# DDS_OUT_channel.net
KiCad netlist of a schematic drawn in Altium Designer
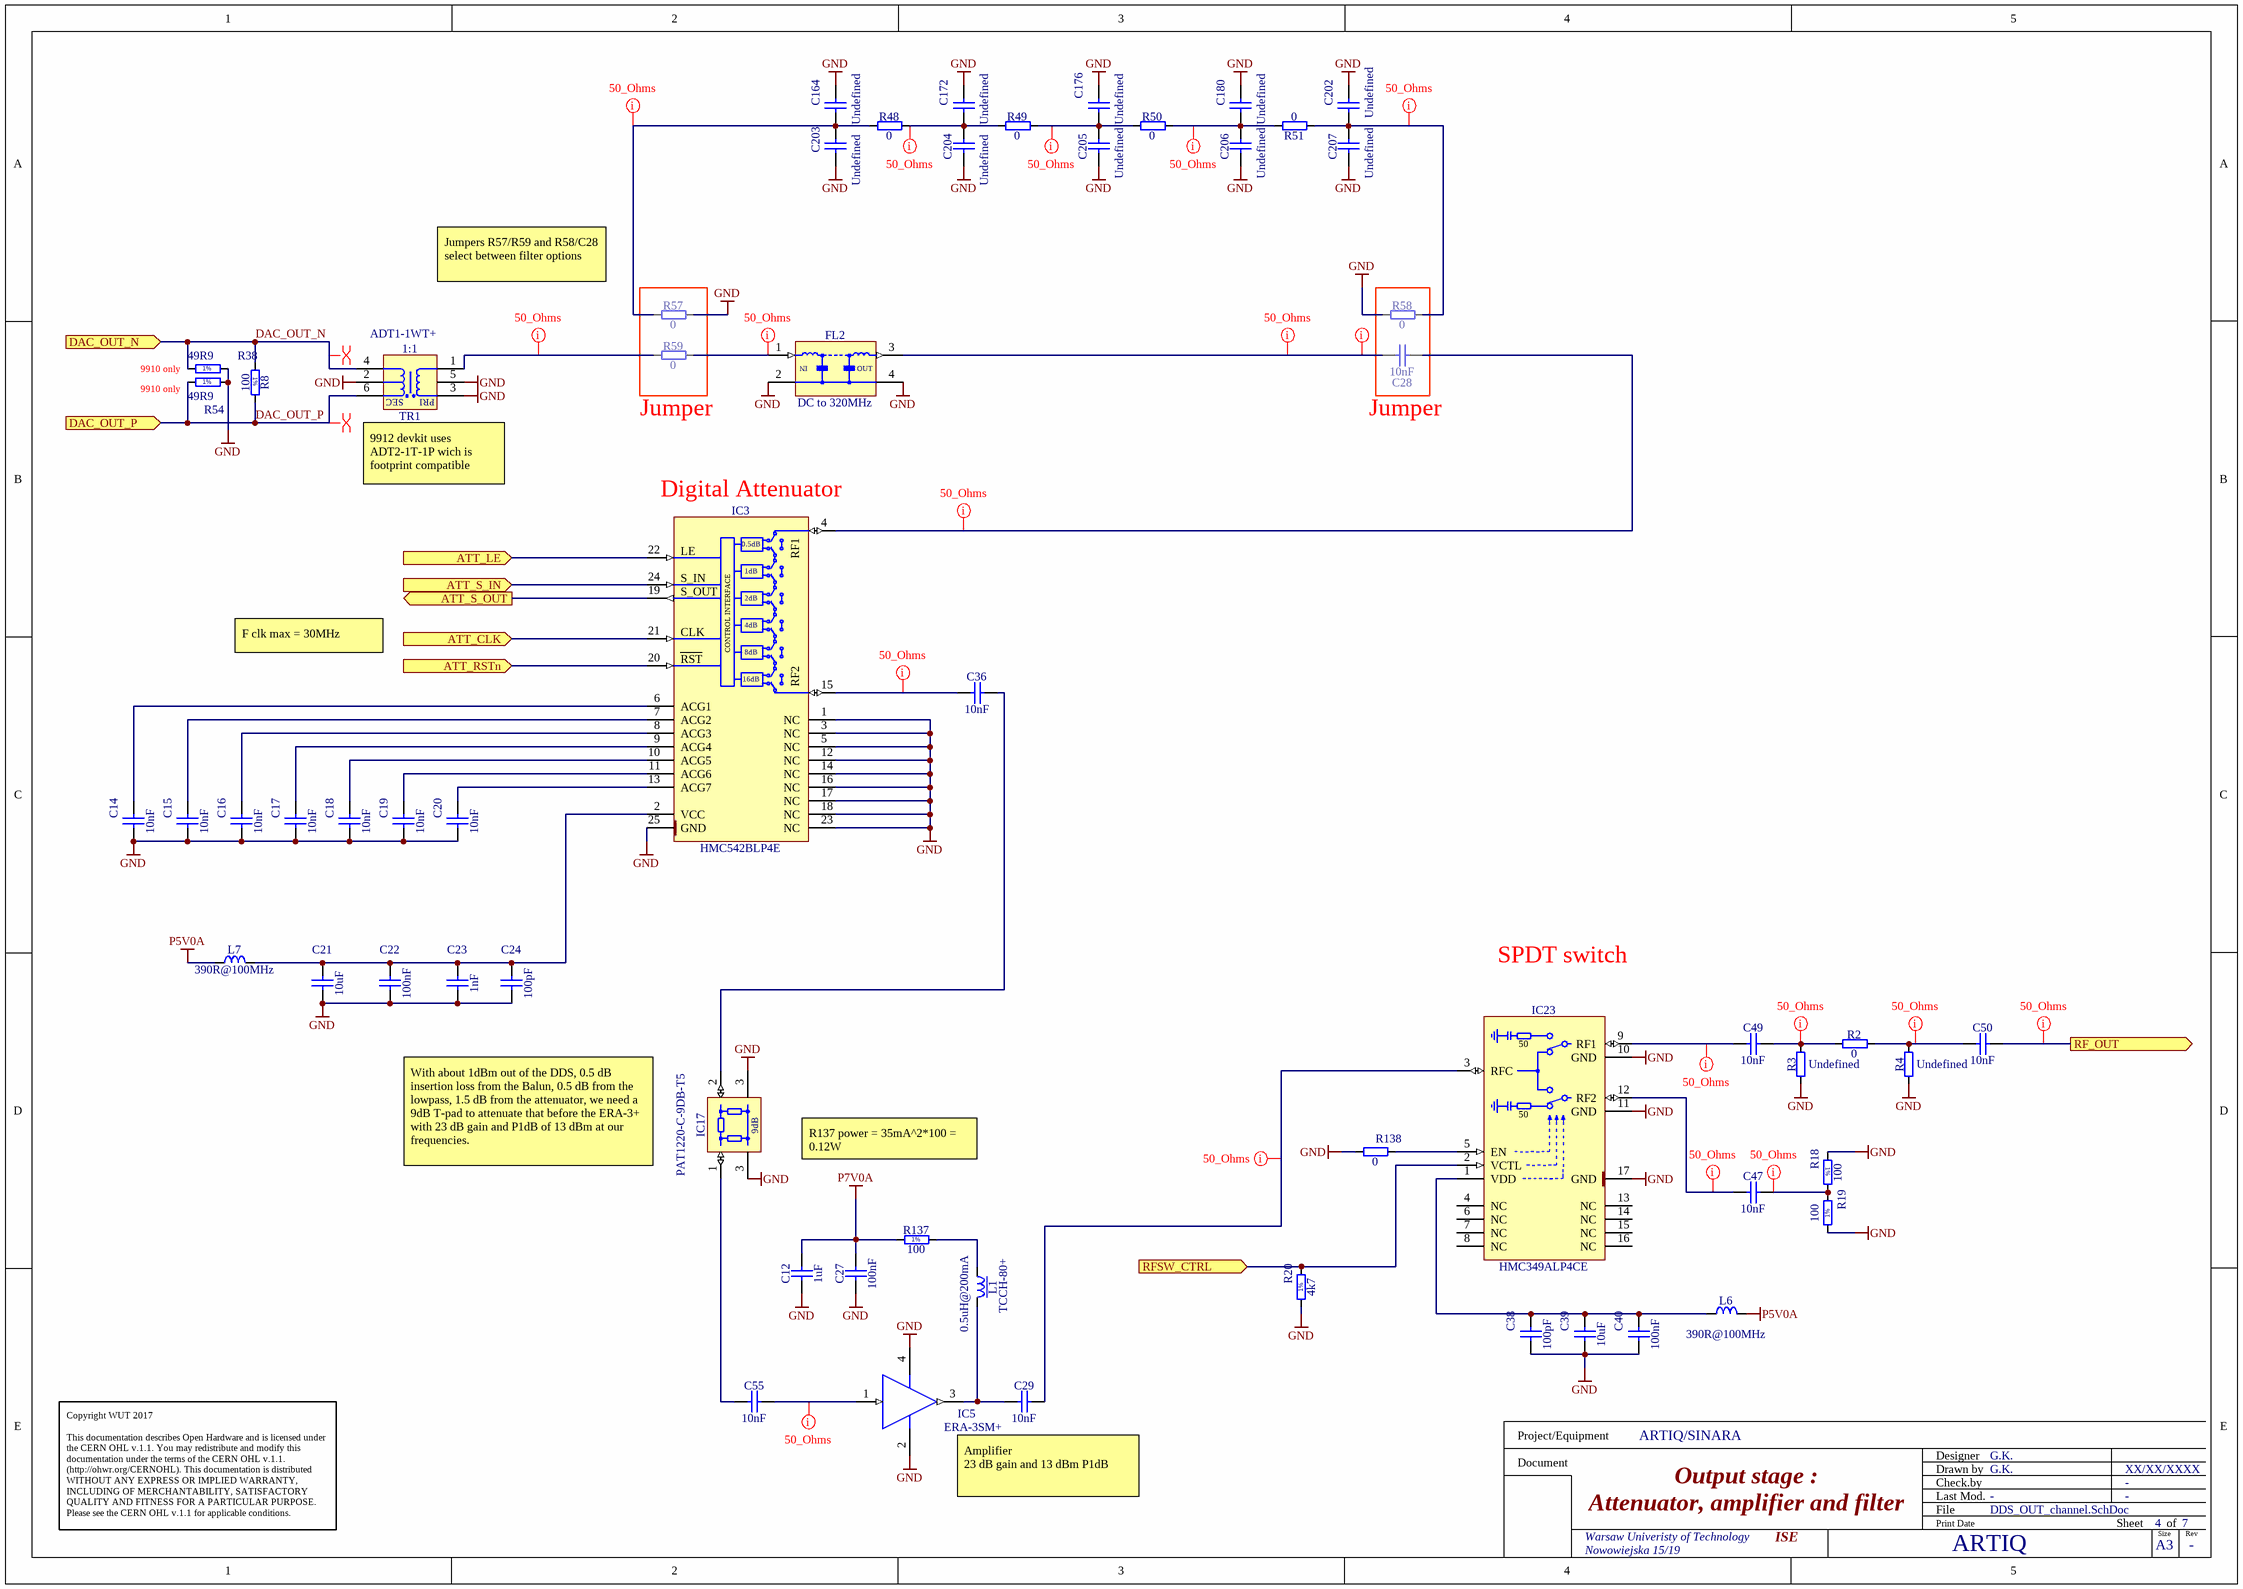
[diagram p0: DDS_OUT_channel.SchDoc]

(export (version "E")
  (design (tool "Eeschema 10.0.6"))
  (components
    (comp (ref "C12")
      (value "1uF")
      (footprint "CAPC2012X140N")
      (description "Non-polarised capacitor")
      (fields
        (field (name "PART NUMBER") "CC0805_1UF_35V_20%_X7R")
        (field (name "VOLTAGE") "35V")
        (field (name "AUTHOR") "CERN DEM JLC")
      )
      (libsource (lib "Capacitors") (part "Capacitor - non polarized"))
    )
    (comp (ref "C14")
      (value "10nF")
      (footprint "CAPC1005X55N")
      (description "Non-polarised capacitor")
      (fields
        (field (name "PART NUMBER") "CC0402_10NF_16V_10%_X7R")
        (field (name "VOLTAGE") "16V")
        (field (name "AUTHOR") "CERN DEM JLC")
      )
      (libsource (lib "Capacitors") (part "Capacitor - non polarized"))
    )
    (comp (ref "C15")
      (value "10nF")
      (footprint "CAPC1005X55N")
      (description "Non-polarised capacitor")
      (fields
        (field (name "PART NUMBER") "CC0402_10NF_16V_10%_X7R")
        (field (name "VOLTAGE") "16V")
        (field (name "AUTHOR") "CERN DEM JLC")
      )
      (libsource (lib "Capacitors") (part "Capacitor - non polarized"))
    )
    (comp (ref "C16")
      (value "10nF")
      (footprint "CAPC1005X55N")
      (description "Non-polarised capacitor")
      (fields
        (field (name "PART NUMBER") "CC0402_10NF_16V_10%_X7R")
        (field (name "VOLTAGE") "16V")
        (field (name "AUTHOR") "CERN DEM JLC")
      )
      (libsource (lib "Capacitors") (part "Capacitor - non polarized"))
    )
    (comp (ref "C17")
      (value "10nF")
      (footprint "CAPC1005X55N")
      (description "Non-polarised capacitor")
      (fields
        (field (name "PART NUMBER") "CC0402_10NF_16V_10%_X7R")
        (field (name "VOLTAGE") "16V")
        (field (name "AUTHOR") "CERN DEM JLC")
      )
      (libsource (lib "Capacitors") (part "Capacitor - non polarized"))
    )
    (comp (ref "C18")
      (value "10nF")
      (footprint "CAPC1005X55N")
      (description "Non-polarised capacitor")
      (fields
        (field (name "PART NUMBER") "CC0402_10NF_16V_10%_X7R")
        (field (name "VOLTAGE") "16V")
        (field (name "AUTHOR") "CERN DEM JLC")
      )
      (libsource (lib "Capacitors") (part "Capacitor - non polarized"))
    )
    (comp (ref "C19")
      (value "10nF")
      (footprint "CAPC1005X55N")
      (description "Non-polarised capacitor")
      (fields
        (field (name "PART NUMBER") "CC0402_10NF_16V_10%_X7R")
        (field (name "VOLTAGE") "16V")
        (field (name "AUTHOR") "CERN DEM JLC")
      )
      (libsource (lib "Capacitors") (part "Capacitor - non polarized"))
    )
    (comp (ref "C20")
      (value "10nF")
      (footprint "CAPC1005X55N")
      (description "Non-polarised capacitor")
      (fields
        (field (name "PART NUMBER") "CC0402_10NF_16V_10%_X7R")
        (field (name "VOLTAGE") "16V")
        (field (name "AUTHOR") "CERN DEM JLC")
      )
      (libsource (lib "Capacitors") (part "Capacitor - non polarized"))
    )
    (comp (ref "C21")
      (value "10uF")
      (footprint "CAPC1608X80N")
      (description "Non-polarised capacitor")
      (fields
        (field (name "PART NUMBER") "CC0603_10UF_16V_20%_X5R")
        (field (name "VOLTAGE") "16V")
        (field (name "AUTHOR") "CERN DEM MR")
      )
      (libsource (lib "Capacitors") (part "Capacitor - non polarized"))
    )
    (comp (ref "C22")
      (value "100nF")
      (footprint "CAPC1005X55N")
      (description "Non-polarised capacitor")
      (fields
        (field (name "PART NUMBER") "CC0402_100NF_16V_10%_X7R")
        (field (name "VOLTAGE") "16V")
        (field (name "AUTHOR") "CERN DEM JLC")
      )
      (libsource (lib "Capacitors") (part "Capacitor - non polarized"))
    )
    (comp (ref "C23")
      (value "1nF")
      (footprint "CAPC1005X55N")
      (description "Non-polarised capacitor")
      (fields
        (field (name "PART NUMBER") "CC0402_1NF_50V_10%_X7R")
        (field (name "VOLTAGE") "50V")
        (field (name "AUTHOR") "CERN DEM JLC")
      )
      (libsource (lib "Capacitors") (part "Capacitor - non polarized"))
    )
    (comp (ref "C24")
      (value "100pF")
      (footprint "CAPC1005X55N")
      (description "Non-polarised capacitor")
      (fields
        (field (name "PART NUMBER") "CC0402_100PF_50V_5%_C0G")
        (field (name "VOLTAGE") "50V")
        (field (name "AUTHOR") "CERN DEM JLC")
      )
      (libsource (lib "Capacitors") (part "Capacitor - non polarized"))
    )
    (comp (ref "C27")
      (value "100nF")
      (footprint "CAPC1005X55N")
      (description "Non-polarised capacitor")
      (fields
        (field (name "PART NUMBER") "CC0402_100NF_16V_10%_X5R")
        (field (name "VOLTAGE") "16V")
        (field (name "AUTHOR") "CERN DEM JLC")
      )
      (libsource (lib "Capacitors") (part "Capacitor - non polarized"))
    )
    (comp (ref "C28")
      (value "10nF")
      (footprint "CAPC1005X55N")
      (description "Non-polarised capacitor")
      (fields
        (field (name "PART NUMBER") "CC0402_10NF_16V_10%_X7R")
        (field (name "VOLTAGE") "16V")
        (field (name "AUTHOR") "CERN DEM JLC")
      )
      (libsource (lib "Capacitors") (part "Capacitor - non polarized"))
    )
    (comp (ref "C29")
      (value "10nF")
      (footprint "CAPC1005X55N")
      (description "Non-polarised capacitor")
      (fields
        (field (name "PART NUMBER") "CC0402_10NF_16V_10%_X7R")
        (field (name "VOLTAGE") "16V")
        (field (name "AUTHOR") "CERN DEM JLC")
      )
      (libsource (lib "Capacitors") (part "Capacitor - non polarized"))
    )
    (comp (ref "C36")
      (value "10nF")
      (footprint "CAPC1005X55N")
      (description "Non-polarised capacitor")
      (fields
        (field (name "PART NUMBER") "CC0402_10NF_16V_10%_X7R")
        (field (name "VOLTAGE") "16V")
        (field (name "AUTHOR") "CERN DEM JLC")
      )
      (libsource (lib "Capacitors") (part "Capacitor - non polarized"))
    )
    (comp (ref "C38")
      (value "100pF")
      (footprint "CAPC1005X55N")
      (description "Non-polarised capacitor")
      (fields
        (field (name "PART NUMBER") "CC0402_100PF_50V_5%_C0G")
        (field (name "VOLTAGE") "50V")
        (field (name "AUTHOR") "CERN DEM JLC")
      )
      (libsource (lib "Capacitors") (part "Capacitor - non polarized"))
    )
    (comp (ref "C39")
      (value "10uF")
      (footprint "CAPC1608X80N")
      (description "Non-polarised capacitor")
      (fields
        (field (name "PART NUMBER") "CC0603_10UF_16V_20%_X5R")
        (field (name "VOLTAGE") "16V")
        (field (name "AUTHOR") "CERN DEM MR")
      )
      (libsource (lib "Capacitors") (part "Capacitor - non polarized"))
    )
    (comp (ref "C40")
      (value "100nF")
      (footprint "CAPC1005X55N")
      (description "Non-polarised capacitor")
      (fields
        (field (name "PART NUMBER") "CC0402_100NF_16V_10%_X5R")
        (field (name "VOLTAGE") "16V")
        (field (name "AUTHOR") "CERN DEM JLC")
      )
      (libsource (lib "Capacitors") (part "Capacitor - non polarized"))
    )
    (comp (ref "C47")
      (value "10nF")
      (footprint "CAPC1005X55N")
      (description "Non-polarised capacitor")
      (fields
        (field (name "PART NUMBER") "CC0402_10NF_16V_10%_X7R")
        (field (name "VOLTAGE") "16V")
        (field (name "AUTHOR") "CERN DEM JLC")
      )
      (libsource (lib "Capacitors") (part "Capacitor - non polarized"))
    )
    (comp (ref "C49")
      (value "10nF")
      (footprint "CAPC1005X55N")
      (description "Non-polarised capacitor")
      (fields
        (field (name "PART NUMBER") "CC0402_10NF_16V_10%_X7R")
        (field (name "VOLTAGE") "16V")
        (field (name "AUTHOR") "CERN DEM JLC")
      )
      (libsource (lib "Capacitors") (part "Capacitor - non polarized"))
    )
    (comp (ref "C50")
      (value "10nF")
      (footprint "CAPC1005X55N")
      (description "Non-polarised capacitor")
      (fields
        (field (name "PART NUMBER") "CC0402_10NF_16V_10%_X7R")
        (field (name "VOLTAGE") "16V")
        (field (name "AUTHOR") "CERN DEM JLC")
      )
      (libsource (lib "Capacitors") (part "Capacitor - non polarized"))
    )
    (comp (ref "C55")
      (value "10nF")
      (footprint "CAPC1005X55N")
      (description "Non-polarised capacitor")
      (fields
        (field (name "PART NUMBER") "CC0402_10NF_16V_10%_X7R")
        (field (name "VOLTAGE") "16V")
        (field (name "AUTHOR") "CERN DEM JLC")
      )
      (libsource (lib "Capacitors") (part "Capacitor - non polarized"))
    )
    (comp (ref "C164")
      (value "Undefined")
      (footprint "CAPC1005X55N")
      (description "Non-polarised capacitor")
      (fields (field (name "PART NUMBER") "CC0402_NO-VALUE") (field (name "AUTHOR") "CERN DEM JLC"))
      (libsource (lib "Capacitors") (part "Capacitor - non polarized"))
    )
    (comp (ref "C172")
      (value "Undefined")
      (footprint "CAPC1005X55N")
      (description "Non-polarised capacitor")
      (fields (field (name "PART NUMBER") "CC0402_NO-VALUE") (field (name "AUTHOR") "CERN DEM JLC"))
      (libsource (lib "Capacitors") (part "Capacitor - non polarized"))
    )
    (comp (ref "C176")
      (value "Undefined")
      (footprint "CAPC1005X55N")
      (description "Non-polarised capacitor")
      (fields (field (name "PART NUMBER") "CC0402_NO-VALUE") (field (name "AUTHOR") "CERN DEM JLC"))
      (libsource (lib "Capacitors") (part "Capacitor - non polarized"))
    )
    (comp (ref "C180")
      (value "Undefined")
      (footprint "CAPC1005X55N")
      (description "Non-polarised capacitor")
      (fields (field (name "PART NUMBER") "CC0402_NO-VALUE") (field (name "AUTHOR") "CERN DEM JLC"))
      (libsource (lib "Capacitors") (part "Capacitor - non polarized"))
    )
    (comp (ref "C202")
      (value "Undefined")
      (footprint "CAPC1005X55N")
      (description "Non-polarised capacitor")
      (fields (field (name "PART NUMBER") "CC0402_NO-VALUE") (field (name "AUTHOR") "CERN DEM JLC"))
      (libsource (lib "Capacitors") (part "Capacitor - non polarized"))
    )
    (comp (ref "C203")
      (value "Undefined")
      (footprint "CAPC1005X55N")
      (description "Non-polarised capacitor")
      (fields (field (name "PART NUMBER") "CC0402_NO-VALUE") (field (name "AUTHOR") "CERN DEM JLC"))
      (libsource (lib "Capacitors") (part "Capacitor - non polarized"))
    )
    (comp (ref "C204")
      (value "Undefined")
      (footprint "CAPC1005X55N")
      (description "Non-polarised capacitor")
      (fields (field (name "PART NUMBER") "CC0402_NO-VALUE") (field (name "AUTHOR") "CERN DEM JLC"))
      (libsource (lib "Capacitors") (part "Capacitor - non polarized"))
    )
    (comp (ref "C205")
      (value "Undefined")
      (footprint "CAPC1005X55N")
      (description "Non-polarised capacitor")
      (fields (field (name "PART NUMBER") "CC0402_NO-VALUE") (field (name "AUTHOR") "CERN DEM JLC"))
      (libsource (lib "Capacitors") (part "Capacitor - non polarized"))
    )
    (comp (ref "C206")
      (value "Undefined")
      (footprint "CAPC1005X55N")
      (description "Non-polarised capacitor")
      (fields (field (name "PART NUMBER") "CC0402_NO-VALUE") (field (name "AUTHOR") "CERN DEM JLC"))
      (libsource (lib "Capacitors") (part "Capacitor - non polarized"))
    )
    (comp (ref "C207")
      (value "Undefined")
      (footprint "CAPC1005X55N")
      (description "Non-polarised capacitor")
      (fields (field (name "PART NUMBER") "CC0402_NO-VALUE") (field (name "AUTHOR") "CERN DEM JLC"))
      (libsource (lib "Capacitors") (part "Capacitor - non polarized"))
    )
    (comp (ref "FL2")
      (value "DC to 320MHz")
      (footprint "FIL_MINI-CIRCUITS_FV1206")
      (description "50 Ohm DC to 320MHz Low Pass Filter")
      (fields
        (field (name "PART NUMBER") "FIL_MINI-CIRCUITS_LFCN-320")
        (field (name "MANUFACTURER") "MINI-CIRCUITS")
        (field (name "AUTHOR") "CERN DEM JLC")
      )
      (libsource (lib "LIBRARY_SCH") (part "FIL_MINI-CIRCUITS_LFCN-320"))
    )
    (comp (ref "IC3")
      (value "HMC542BLP4E")
      (footprint "QFN50P400X400X100-25N-S295")
      (description "0.5dB LSB GaAs MMIC 6-bit Digital Serial Control Attenuator, DC - 4GHz")
      (fields (field (name "MANUFACTURER") "HITTITE MICROWAVE CORP") (field (name "AUTHOR") "CERN DEM JMW"))
      (libsource (lib "ICs And Semiconductors") (part "HMC542BLP4E"))
    )
    (comp (ref "IC5")
      (value "ERA-3SM+")
      (footprint "MINI-CIRCUITS_WW107")
      (description "DC-3GHz Monolithic Amplifier")
      (fields (field (name "MANUFACTURER") "MINI-CIRCUITS") (field (name "AUTHOR") "GK"))
      (libsource (lib "LIBRARY_SCH") (part "RF_ERA-3SM+"))
    )
    (comp (ref "IC17")
      (value "PAT1220-C-9DB-T5")
      (footprint "SUSUMU_PAT1220")
      (description "DC to 10GHz, 100mw, 50 Ohm, 9dB, Precision chip attenuator")
      (fields (field (name "MANUFACTURER") "SUSUMU") (field (name "AUTHOR") "GK"))
      (libsource (lib "LIBRARY_SCH") (part "RF_PAT1220-C-9DB-T5"))
    )
    (comp (ref "IC23")
      (value "HMC349ALP4CE")
      (footprint "QFN65P400X400X100-17N-S255")
      (description "DC-4GHz High Isolation SPDT Non-Reflective Switch")
      (fields (field (name "MANUFACTURER") "ANALOG DEVICES") (field (name "AUTHOR") "CERN DEM JLC"))
      (libsource (lib "ICs And Semiconductors") (part "HMC349ALP4CE"))
    )
    (comp (ref "L1")
      (value "0.5uH@200mA")
      (footprint "IND_MINI-CIRCUITS_GU1604")
      (description "50 Ohms, 50 to 8200 MHz RF Choke")
      (fields
        (field (name "PART NUMBER") "IND_MINI-CIRCUITS_TCCH-80+")
        (field (name "POWER") "200mA")
        (field (name "MANUFACTURER PART NUMBER") "TCCH-80+")
        (field (name "AUTHOR") "CERN DEM JLC")
      )
      (libsource (lib "Inductors & Transformers") (part "IND_MINI-CIRCUITS_TCCH-80+"))
    )
    (comp (ref "L6")
      (value "390R@100MHz")
      (footprint "INDC1608X95N")
      (description "Inductor")
      (fields
        (field (name "PART NUMBER") "IND0603_TDK_MPZ1608R391A")
        (field (name "POWER") "1.2A")
        (field (name "AUTHOR") "CERN DEM JLC")
      )
      (libsource (lib "Inductors & Transformers") (part "Inductor"))
    )
    (comp (ref "L7")
      (value "390R@100MHz")
      (footprint "INDC1608X95N")
      (description "Inductor")
      (fields
        (field (name "PART NUMBER") "IND0603_TDK_MPZ1608R391A")
        (field (name "POWER") "1.2A")
        (field (name "AUTHOR") "CERN DEM JLC")
      )
      (libsource (lib "Inductors & Transformers") (part "Inductor"))
    )
    (comp (ref "R2")
      (value "0")
      (footprint "RESC1005X40N")
      (description "Resistor")
      (fields
        (field (name "PART NUMBER") "R0402_0R_JUMPER")
        (field (name "MANUFACTURER") "GENERIC")
        (field (name "AUTHOR") "CERN DEM JLC")
      )
      (libsource (lib "Resistors") (part "Resistor"))
    )
    (comp (ref "R3")
      (value "Undefined")
      (footprint "RESC1005X40N")
      (description "Resistor")
      (fields (field (name "PART NUMBER") "R0402_NO-VALUE") (field (name "AUTHOR") "CERN DEM JLC"))
      (libsource (lib "Resistors") (part "Resistor"))
    )
    (comp (ref "R4")
      (value "Undefined")
      (footprint "RESC1005X40N")
      (description "Resistor")
      (fields (field (name "PART NUMBER") "R0402_NO-VALUE") (field (name "AUTHOR") "CERN DEM JLC"))
      (libsource (lib "Resistors") (part "Resistor"))
    )
    (comp (ref "R8")
      (value "100")
      (footprint "RESC1005X40N")
      (description "Resistor - 1%")
      (fields
        (field (name "PART NUMBER") "R0402_100R_1%_0.0625W_100PPM")
        (field (name "POWER") "0.0625W")
        (field (name "AUTHOR") "CERN DEM JLC")
      )
      (libsource (lib "Resistors") (part "Resistor - 1%"))
    )
    (comp (ref "R18")
      (value "100")
      (footprint "RESC1005X40N")
      (description "Resistor - 1%")
      (fields
        (field (name "PART NUMBER") "R0402_100R_1%_0.0625W_100PPM")
        (field (name "POWER") "0.0625W")
        (field (name "AUTHOR") "CERN DEM JLC")
      )
      (libsource (lib "Resistors") (part "Resistor - 1%"))
    )
    (comp (ref "R19")
      (value "100")
      (footprint "RESC1005X40N")
      (description "Resistor - 1%")
      (fields
        (field (name "PART NUMBER") "R0402_100R_1%_0.0625W_100PPM")
        (field (name "POWER") "0.0625W")
        (field (name "AUTHOR") "CERN DEM JLC")
      )
      (libsource (lib "Resistors") (part "Resistor - 1%"))
    )
    (comp (ref "R20")
      (value "4k7")
      (footprint "RESC1005X40N")
      (description "Resistor - 1%")
      (fields
        (field (name "PART NUMBER") "R0402_4K7_1%_0.0625W_100PPM")
        (field (name "POWER") "0.0625W")
        (field (name "AUTHOR") "CERN DEM JLC")
      )
      (libsource (lib "Resistors") (part "Resistor - 1%"))
    )
    (comp (ref "R38")
      (value "49R9")
      (footprint "RESC1005X40N")
      (description "Resistor - 1%")
      (fields
        (field (name "PART NUMBER") "R0402_49R9_1%_0.0625W_100PPM")
        (field (name "POWER") "0.0625W")
        (field (name "AUTHOR") "CERN DEM JLC")
      )
      (libsource (lib "Resistors") (part "Resistor - 1%"))
    )
    (comp (ref "R48")
      (value "0")
      (footprint "RESC1005X40N")
      (description "Resistor")
      (fields
        (field (name "PART NUMBER") "R0402_0R_JUMPER")
        (field (name "MANUFACTURER") "GENERIC")
        (field (name "AUTHOR") "CERN DEM JLC")
      )
      (libsource (lib "Resistors") (part "Resistor"))
    )
    (comp (ref "R49")
      (value "0")
      (footprint "RESC1005X40N")
      (description "Resistor")
      (fields
        (field (name "PART NUMBER") "R0402_0R_JUMPER")
        (field (name "MANUFACTURER") "GENERIC")
        (field (name "AUTHOR") "CERN DEM JLC")
      )
      (libsource (lib "Resistors") (part "Resistor"))
    )
    (comp (ref "R50")
      (value "0")
      (footprint "RESC1005X40N")
      (description "Resistor")
      (fields
        (field (name "PART NUMBER") "R0402_0R_JUMPER")
        (field (name "MANUFACTURER") "GENERIC")
        (field (name "AUTHOR") "CERN DEM JLC")
      )
      (libsource (lib "Resistors") (part "Resistor"))
    )
    (comp (ref "R51")
      (value "0")
      (footprint "RESC1005X40N")
      (description "Resistor")
      (fields
        (field (name "PART NUMBER") "R0402_0R_JUMPER")
        (field (name "MANUFACTURER") "GENERIC")
        (field (name "AUTHOR") "CERN DEM JLC")
      )
      (libsource (lib "Resistors") (part "Resistor"))
    )
    (comp (ref "R54")
      (value "49R9")
      (footprint "RESC1005X40N")
      (description "Resistor - 1%")
      (fields
        (field (name "PART NUMBER") "R0402_49R9_1%_0.0625W_100PPM")
        (field (name "POWER") "0.0625W")
        (field (name "AUTHOR") "CERN DEM JLC")
      )
      (libsource (lib "Resistors") (part "Resistor - 1%"))
    )
    (comp (ref "R57")
      (value "0")
      (footprint "RESC1005X40N")
      (description "Resistor")
      (fields
        (field (name "PART NUMBER") "R0402_0R_JUMPER")
        (field (name "MANUFACTURER") "GENERIC")
        (field (name "AUTHOR") "CERN DEM JLC")
      )
      (libsource (lib "Resistors") (part "Resistor"))
    )
    (comp (ref "R58")
      (value "0")
      (footprint "RESC1005X40N")
      (description "Resistor")
      (fields
        (field (name "PART NUMBER") "R0402_0R_JUMPER")
        (field (name "MANUFACTURER") "GENERIC")
        (field (name "AUTHOR") "CERN DEM JLC")
      )
      (libsource (lib "Resistors") (part "Resistor"))
    )
    (comp (ref "R59")
      (value "0")
      (footprint "RESC1005X40N")
      (description "Resistor")
      (fields
        (field (name "PART NUMBER") "R0402_0R_JUMPER")
        (field (name "MANUFACTURER") "GENERIC")
        (field (name "AUTHOR") "CERN DEM JLC")
      )
      (libsource (lib "Resistors") (part "Resistor"))
    )
    (comp (ref "R137")
      (value "100")
      (footprint "RESC3216X65N")
      (description "Resistor - 1%")
      (fields
        (field (name "PART NUMBER") "R1206_100R_1%_0.5W_100PPM_VISHAY_CRCW-HP e3")
        (field (name "POWER") "0.5W")
        (field (name "AUTHOR") "CERN DEM JLC")
      )
      (libsource (lib "Resistors") (part "Resistor - 1%"))
    )
    (comp (ref "R138")
      (value "0")
      (footprint "RESC1005X40N")
      (description "Resistor")
      (fields
        (field (name "PART NUMBER") "R0402_0R_JUMPER")
        (field (name "MANUFACTURER") "GENERIC")
        (field (name "AUTHOR") "CERN DEM JLC")
      )
      (libsource (lib "Resistors") (part "Resistor"))
    )
    (comp (ref "TR1")
      (value "1:1")
      (footprint "XFMR_MINI-CIRCUITS_CD542")
      (description "75 Ohm 0.4 To 800MHz RF Transformers")
      (fields
        (field (name "PART NUMBER") "XFMR_MINI-CIRCUITS_ADT1-1WT+")
        (field (name "MANUFACTURER") "MINI-CIRCUITS")
        (field (name "MANUFACTURER PART NUMBER") "ADT1-1WT+")
        (field (name "AUTHOR") "CERN DEM JLC")
      )
      (libsource (lib "Inductors & Transformers") (part "XFMR_MINI-CIRCUITS_ADT1-1WT+"))
    )
  )
  (nets
    (net (code "1") (name "/ATT_CLK") (class "Default")
      (node (ref "IC3") (pin "21") (pinfunction "SHIFT_CLOCK_21") (pintype "input"))
    )
    (net (code "2") (name "/ATT_LE") (class "Default")
      (node (ref "IC3") (pin "22") (pinfunction "LATCH_ENABLE_22") (pintype "input"))
    )
    (net (code "3") (name "/ATT_RSTn") (class "Default")
      (node (ref "IC3") (pin "20") (pinfunction "~{RESET}_20") (pintype "input"))
    )
    (net (code "4") (name "/ATT_S_IN") (class "Default")
      (node (ref "IC3") (pin "24") (pinfunction "SERIAL_INPUT_24") (pintype "input"))
    )
    (net (code "5") (name "/ATT_S_OUT") (class "Default")
      (node (ref "IC3") (pin "19") (pinfunction "SERIAL_OUTPUT_19") (pintype "output"))
    )
    (net (code "6") (name "/DAC_OUT_N") (class "Default")
      (node (ref "R38") (pin "1") (pinfunction "1_1") (pintype "passive"))
      (node (ref "R8") (pin "1") (pinfunction "1_1") (pintype "passive"))
      (node (ref "TR1") (pin "4") (pinfunction "S_4") (pintype "passive"))
    )
    (net (code "7") (name "/DAC_OUT_P") (class "Default")
      (node (ref "R54") (pin "1") (pinfunction "1_1") (pintype "passive"))
      (node (ref "R8") (pin "2") (pinfunction "2_2") (pintype "passive"))
      (node (ref "TR1") (pin "6") (pinfunction "SDOT_6") (pintype "passive"))
    )
    (net (code "8") (name "/RFSW_CTRL") (class "Default")
      (node (ref "IC23") (pin "2") (pinfunction "VCTL_2") (pintype "input"))
      (node (ref "R20") (pin "2") (pinfunction "2_2") (pintype "passive"))
    )
    (net (code "9") (name "/RF_OUT") (class "Default")
      (node (ref "C50") (pin "2") (pinfunction "2_2") (pintype "passive"))
    )
    (net (code "10") (name "GND") (class "Default")
      (node (ref "C12") (pin "1") (pinfunction "1_1") (pintype "passive"))
      (node (ref "C14") (pin "1") (pinfunction "1_1") (pintype "passive"))
      (node (ref "C15") (pin "1") (pinfunction "1_1") (pintype "passive"))
      (node (ref "C16") (pin "1") (pinfunction "1_1") (pintype "passive"))
      (node (ref "C164") (pin "2") (pinfunction "2_2") (pintype "passive"))
      (node (ref "C17") (pin "1") (pinfunction "1_1") (pintype "passive"))
      (node (ref "C172") (pin "2") (pinfunction "2_2") (pintype "passive"))
      (node (ref "C176") (pin "2") (pinfunction "2_2") (pintype "passive"))
      (node (ref "C18") (pin "1") (pinfunction "1_1") (pintype "passive"))
      (node (ref "C180") (pin "2") (pinfunction "2_2") (pintype "passive"))
      (node (ref "C19") (pin "1") (pinfunction "1_1") (pintype "passive"))
      (node (ref "C20") (pin "1") (pinfunction "1_1") (pintype "passive"))
      (node (ref "C202") (pin "2") (pinfunction "2_2") (pintype "passive"))
      (node (ref "C203") (pin "1") (pinfunction "1_1") (pintype "passive"))
      (node (ref "C204") (pin "1") (pinfunction "1_1") (pintype "passive"))
      (node (ref "C205") (pin "1") (pinfunction "1_1") (pintype "passive"))
      (node (ref "C206") (pin "1") (pinfunction "1_1") (pintype "passive"))
      (node (ref "C207") (pin "1") (pinfunction "1_1") (pintype "passive"))
      (node (ref "C21") (pin "1") (pinfunction "1_1") (pintype "passive"))
      (node (ref "C22") (pin "1") (pinfunction "1_1") (pintype "passive"))
      (node (ref "C23") (pin "1") (pinfunction "1_1") (pintype "passive"))
      (node (ref "C24") (pin "1") (pinfunction "1_1") (pintype "passive"))
      (node (ref "C27") (pin "1") (pinfunction "1_1") (pintype "passive"))
      (node (ref "C38") (pin "2") (pinfunction "2_2") (pintype "passive"))
      (node (ref "C39") (pin "1") (pinfunction "1_1") (pintype "passive"))
      (node (ref "C40") (pin "1") (pinfunction "1_1") (pintype "passive"))
      (node (ref "FL2") (pin "2") (pinfunction "GND_2") (pintype "power_in"))
      (node (ref "FL2") (pin "4") (pinfunction "GND_4") (pintype "power_in"))
      (node (ref "IC17") (pin "3") (pinfunction "GND_3") (pintype "passive"))
      (node (ref "IC23") (pin "10") (pinfunction "GND_10") (pintype "power_in"))
      (node (ref "IC23") (pin "11") (pinfunction "GND_11") (pintype "power_in"))
      (node (ref "IC23") (pin "17") (pinfunction "GND_17") (pintype "power_in"))
      (node (ref "IC3") (pin "1") (pinfunction "NC_1") (pintype "passive"))
      (node (ref "IC3") (pin "12") (pinfunction "NC_12") (pintype "passive"))
      (node (ref "IC3") (pin "14") (pinfunction "NC_14") (pintype "passive"))
      (node (ref "IC3") (pin "16") (pinfunction "NC_16") (pintype "passive"))
      (node (ref "IC3") (pin "17") (pinfunction "NC_17") (pintype "passive"))
      (node (ref "IC3") (pin "18") (pinfunction "NC_18") (pintype "passive"))
      (node (ref "IC3") (pin "23") (pinfunction "NC_23") (pintype "passive"))
      (node (ref "IC3") (pin "25") (pinfunction "GND_25") (pintype "power_in"))
      (node (ref "IC3") (pin "3") (pinfunction "NC_3") (pintype "passive"))
      (node (ref "IC3") (pin "5") (pinfunction "NC_5") (pintype "passive"))
      (node (ref "IC5") (pin "2") (pinfunction "GND_2") (pintype "power_in"))
      (node (ref "IC5") (pin "4") (pinfunction "GND_4") (pintype "power_in"))
      (node (ref "R138") (pin "1") (pinfunction "1_1") (pintype "passive"))
      (node (ref "R18") (pin "1") (pinfunction "1_1") (pintype "passive"))
      (node (ref "R19") (pin "1") (pinfunction "1_1") (pintype "passive"))
      (node (ref "R20") (pin "1") (pinfunction "1_1") (pintype "passive"))
      (node (ref "R3") (pin "1") (pinfunction "1_1") (pintype "passive"))
      (node (ref "R38") (pin "2") (pinfunction "2_2") (pintype "passive"))
      (node (ref "R4") (pin "1") (pinfunction "1_1") (pintype "passive"))
      (node (ref "R54") (pin "2") (pinfunction "2_2") (pintype "passive"))
      (node (ref "R57") (pin "2") (pinfunction "2_2") (pintype "passive"))
      (node (ref "R58") (pin "2") (pinfunction "2_2") (pintype "passive"))
      (node (ref "TR1") (pin "2") (pinfunction "SCT_2") (pintype "passive"))
      (node (ref "TR1") (pin "3") (pinfunction "PDOT_3") (pintype "passive"))
      (node (ref "TR1") (pin "5") (pinfunction "NC_5") (pintype "passive"))
    )
    (net (code "11") (name "Net-(C47-Pad2)") (class "Default")
      (node (ref "C47") (pin "2") (pinfunction "2_2") (pintype "passive"))
      (node (ref "R18") (pin "2") (pinfunction "2_2") (pintype "passive"))
      (node (ref "R19") (pin "2") (pinfunction "2_2") (pintype "passive"))
    )
    (net (code "12") (name "Net-(C49-Pad2)") (class "Default")
      (node (ref "C49") (pin "2") (pinfunction "2_2") (pintype "passive"))
      (node (ref "R2") (pin "1") (pinfunction "1_1") (pintype "passive"))
      (node (ref "R3") (pin "2") (pinfunction "2_2") (pintype "passive"))
    )
    (net (code "13") (name "Net-(C50-Pad1)") (class "Default")
      (node (ref "C50") (pin "1") (pinfunction "1_1") (pintype "passive"))
      (node (ref "R2") (pin "2") (pinfunction "2_2") (pintype "passive"))
      (node (ref "R4") (pin "2") (pinfunction "2_2") (pintype "passive"))
    )
    (net (code "14") (name "Net-(C164-Pad1)") (class "Default")
      (node (ref "C164") (pin "1") (pinfunction "1_1") (pintype "passive"))
      (node (ref "C203") (pin "2") (pinfunction "2_2") (pintype "passive"))
      (node (ref "R48") (pin "1") (pinfunction "1_1") (pintype "passive"))
      (node (ref "R57") (pin "1") (pinfunction "1_1") (pintype "passive"))
    )
    (net (code "15") (name "Net-(C172-Pad1)") (class "Default")
      (node (ref "C172") (pin "1") (pinfunction "1_1") (pintype "passive"))
      (node (ref "C204") (pin "2") (pinfunction "2_2") (pintype "passive"))
      (node (ref "R48") (pin "2") (pinfunction "2_2") (pintype "passive"))
      (node (ref "R49") (pin "1") (pinfunction "1_1") (pintype "passive"))
    )
    (net (code "16") (name "Net-(C176-Pad1)") (class "Default")
      (node (ref "C176") (pin "1") (pinfunction "1_1") (pintype "passive"))
      (node (ref "C205") (pin "2") (pinfunction "2_2") (pintype "passive"))
      (node (ref "R49") (pin "2") (pinfunction "2_2") (pintype "passive"))
      (node (ref "R50") (pin "1") (pinfunction "1_1") (pintype "passive"))
    )
    (net (code "17") (name "Net-(C180-Pad1)") (class "Default")
      (node (ref "C180") (pin "1") (pinfunction "1_1") (pintype "passive"))
      (node (ref "C206") (pin "2") (pinfunction "2_2") (pintype "passive"))
      (node (ref "R50") (pin "2") (pinfunction "2_2") (pintype "passive"))
      (node (ref "R51") (pin "2") (pinfunction "2_2") (pintype "passive"))
    )
    (net (code "18") (name "Net-(C202-Pad1)") (class "Default")
      (node (ref "C202") (pin "1") (pinfunction "1_1") (pintype "passive"))
      (node (ref "C207") (pin "2") (pinfunction "2_2") (pintype "passive"))
      (node (ref "R51") (pin "1") (pinfunction "1_1") (pintype "passive"))
      (node (ref "R58") (pin "1") (pinfunction "1_1") (pintype "passive"))
    )
    (net (code "19") (name "Net-(FL2-RFIN)") (class "Default")
      (node (ref "FL2") (pin "1") (pinfunction "RFIN_1") (pintype "input"))
      (node (ref "R59") (pin "2") (pinfunction "2_2") (pintype "passive"))
    )
    (net (code "20") (name "Net-(FL2-RFOUT)") (class "Default")
      (node (ref "C28") (pin "1") (pinfunction "1_1") (pintype "passive"))
      (node (ref "FL2") (pin "3") (pinfunction "RFOUT_3") (pintype "output"))
    )
    (net (code "21") (name "Net-(IC3-ACG1)") (class "Default")
      (node (ref "C14") (pin "2") (pinfunction "2_2") (pintype "passive"))
      (node (ref "IC3") (pin "6") (pinfunction "ACG1_6") (pintype "passive"))
    )
    (net (code "22") (name "Net-(IC3-ACG2)") (class "Default")
      (node (ref "C15") (pin "2") (pinfunction "2_2") (pintype "passive"))
      (node (ref "IC3") (pin "7") (pinfunction "ACG2_7") (pintype "passive"))
    )
    (net (code "23") (name "Net-(IC3-ACG3)") (class "Default")
      (node (ref "C16") (pin "2") (pinfunction "2_2") (pintype "passive"))
      (node (ref "IC3") (pin "8") (pinfunction "ACG3_8") (pintype "passive"))
    )
    (net (code "24") (name "Net-(IC3-ACG4)") (class "Default")
      (node (ref "C17") (pin "2") (pinfunction "2_2") (pintype "passive"))
      (node (ref "IC3") (pin "9") (pinfunction "ACG4_9") (pintype "passive"))
    )
    (net (code "25") (name "Net-(IC3-ACG5)") (class "Default")
      (node (ref "C18") (pin "2") (pinfunction "2_2") (pintype "passive"))
      (node (ref "IC3") (pin "10") (pinfunction "ACG5_10") (pintype "passive"))
    )
    (net (code "26") (name "Net-(IC3-ACG6)") (class "Default")
      (node (ref "C19") (pin "2") (pinfunction "2_2") (pintype "passive"))
      (node (ref "IC3") (pin "11") (pinfunction "ACG6_11") (pintype "passive"))
    )
    (net (code "27") (name "Net-(IC3-ACG7)") (class "Default")
      (node (ref "C20") (pin "2") (pinfunction "2_2") (pintype "passive"))
      (node (ref "IC3") (pin "13") (pinfunction "ACG7_13") (pintype "passive"))
    )
    (net (code "28") (name "Net-(IC3-RF1)") (class "Default")
      (node (ref "C28") (pin "2") (pinfunction "2_2") (pintype "passive"))
      (node (ref "IC3") (pin "4") (pinfunction "RF1_4") (pintype "bidirectional"))
    )
    (net (code "29") (name "Net-(IC3-RF2)") (class "Default")
      (node (ref "C36") (pin "1") (pinfunction "1_1") (pintype "passive"))
      (node (ref "IC3") (pin "15") (pinfunction "RF2_15") (pintype "bidirectional"))
    )
    (net (code "30") (name "Net-(IC3-VCC)") (class "Default")
      (node (ref "C21") (pin "2") (pinfunction "2_2") (pintype "passive"))
      (node (ref "C22") (pin "2") (pinfunction "2_2") (pintype "passive"))
      (node (ref "C23") (pin "2") (pinfunction "2_2") (pintype "passive"))
      (node (ref "C24") (pin "2") (pinfunction "2_2") (pintype "passive"))
      (node (ref "IC3") (pin "2") (pinfunction "VCC_2") (pintype "power_in"))
      (node (ref "L7") (pin "2") (pinfunction "2_2") (pintype "passive"))
    )
    (net (code "31") (name "Net-(IC5-RF_IN)") (class "Default")
      (node (ref "C55") (pin "2") (pinfunction "2_2") (pintype "passive"))
      (node (ref "IC5") (pin "1") (pinfunction "RF_IN_1") (pintype "input"))
    )
    (net (code "32") (name "Net-(IC5-RF_OUT)") (class "Default")
      (node (ref "C29") (pin "1") (pinfunction "1_1") (pintype "passive"))
      (node (ref "IC5") (pin "3") (pinfunction "RF_OUT_3") (pintype "output"))
      (node (ref "L1") (pin "3") (pinfunction "3_3") (pintype "passive"))
    )
    (net (code "33") (name "Net-(IC17-IN)") (class "Default")
      (node (ref "C55") (pin "1") (pinfunction "1_1") (pintype "passive"))
      (node (ref "IC17") (pin "1") (pinfunction "IN_1") (pintype "bidirectional"))
    )
    (net (code "34") (name "Net-(IC17-OUT)") (class "Default")
      (node (ref "C36") (pin "2") (pinfunction "2_2") (pintype "passive"))
      (node (ref "IC17") (pin "2") (pinfunction "OUT_2") (pintype "bidirectional"))
    )
    (net (code "35") (name "Net-(IC23-EN)") (class "Default")
      (node (ref "IC23") (pin "5") (pinfunction "EN_5") (pintype "input"))
      (node (ref "R138") (pin "2") (pinfunction "2_2") (pintype "passive"))
    )
    (net (code "36") (name "Net-(IC23-RF1)") (class "Default")
      (node (ref "C49") (pin "1") (pinfunction "1_1") (pintype "passive"))
      (node (ref "IC23") (pin "9") (pinfunction "RF1_9") (pintype "bidirectional"))
    )
    (net (code "37") (name "Net-(IC23-RF2)") (class "Default")
      (node (ref "C47") (pin "1") (pinfunction "1_1") (pintype "passive"))
      (node (ref "IC23") (pin "12") (pinfunction "RF2_12") (pintype "bidirectional"))
    )
    (net (code "38") (name "Net-(IC23-RFC)") (class "Default")
      (node (ref "C29") (pin "2") (pinfunction "2_2") (pintype "passive"))
      (node (ref "IC23") (pin "3") (pinfunction "RFC_3") (pintype "bidirectional"))
    )
    (net (code "39") (name "Net-(IC23-VDD)") (class "Default")
      (node (ref "C38") (pin "1") (pinfunction "1_1") (pintype "passive"))
      (node (ref "C39") (pin "2") (pinfunction "2_2") (pintype "passive"))
      (node (ref "C40") (pin "2") (pinfunction "2_2") (pintype "passive"))
      (node (ref "IC23") (pin "1") (pinfunction "VDD_1") (pintype "power_in"))
      (node (ref "L6") (pin "1") (pinfunction "1_1") (pintype "passive"))
    )
    (net (code "40") (name "Net-(L1-Pad1)") (class "Default")
      (node (ref "L1") (pin "1") (pinfunction "1_1") (pintype "passive"))
      (node (ref "R137") (pin "2") (pinfunction "2_2") (pintype "passive"))
    )
    (net (code "41") (name "Net-(TR1-P)") (class "Default")
      (node (ref "R59") (pin "1") (pinfunction "1_1") (pintype "passive"))
      (node (ref "TR1") (pin "1") (pinfunction "P_1") (pintype "passive"))
    )
    (net (code "42") (name "P5V0A") (class "Default")
      (node (ref "L6") (pin "2") (pinfunction "2_2") (pintype "passive"))
      (node (ref "L7") (pin "1") (pinfunction "1_1") (pintype "passive"))
    )
    (net (code "43") (name "P7V0A") (class "Default")
      (node (ref "C12") (pin "2") (pinfunction "2_2") (pintype "passive"))
      (node (ref "C27") (pin "2") (pinfunction "2_2") (pintype "passive"))
      (node (ref "R137") (pin "1") (pinfunction "1_1") (pintype "passive"))
    )
    (net (code "44") (name "unconnected-(IC23-NC-Pad4)") (class "Default")
      (node (ref "IC23") (pin "4") (pinfunction "NC_4") (pintype "passive"))
    )
    (net (code "45") (name "unconnected-(IC23-NC-Pad6)") (class "Default")
      (node (ref "IC23") (pin "6") (pinfunction "NC_6") (pintype "passive"))
    )
    (net (code "46") (name "unconnected-(IC23-NC-Pad7)") (class "Default")
      (node (ref "IC23") (pin "7") (pinfunction "NC_7") (pintype "passive"))
    )
    (net (code "47") (name "unconnected-(IC23-NC-Pad8)") (class "Default")
      (node (ref "IC23") (pin "8") (pinfunction "NC_8") (pintype "passive"))
    )
    (net (code "48") (name "unconnected-(IC23-NC-Pad13)") (class "Default")
      (node (ref "IC23") (pin "13") (pinfunction "NC_13") (pintype "passive"))
    )
    (net (code "49") (name "unconnected-(IC23-NC-Pad14)") (class "Default")
      (node (ref "IC23") (pin "14") (pinfunction "NC_14") (pintype "passive"))
    )
    (net (code "50") (name "unconnected-(IC23-NC-Pad15)") (class "Default")
      (node (ref "IC23") (pin "15") (pinfunction "NC_15") (pintype "passive"))
    )
    (net (code "51") (name "unconnected-(IC23-NC-Pad16)") (class "Default")
      (node (ref "IC23") (pin "16") (pinfunction "NC_16") (pintype "passive"))
    )
  )
)
